# PLL.net
KiCad netlist of a schematic drawn in Altium Designer
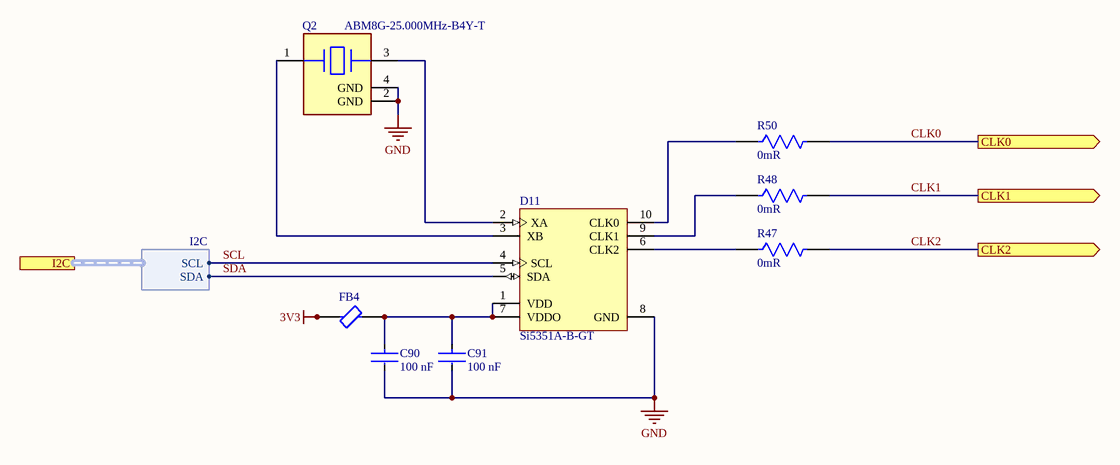
[diagram p0: PLL.SchDoc]

(export (version "E")
  (design (tool "Eeschema 10.0.6"))
  (components
    (comp (ref "C90")
      (value "CC0805KRX7R9BB104")
      (footprint "FP-CC0805-0_85-IPC_A")
      (description "CAP CER 0.1UF 50V X7R 0805")
      (fields (field (name "MANUFACTURER") "Yageo") (field (name "CAPACITANCE") "100 nF"))
      (libsource (lib "SchLib") (part "CMP-2100-03606-3"))
    )
    (comp (ref "C91")
      (value "CC0805KRX7R9BB104")
      (footprint "FP-CC0805-0_85-IPC_A")
      (description "CAP CER 0.1UF 50V X7R 0805")
      (fields (field (name "MANUFACTURER") "Yageo") (field (name "CAPACITANCE") "100 nF"))
      (libsource (lib "SchLib") (part "CMP-2100-03606-3"))
    )
    (comp (ref "D11")
      (value "Si5351A-B-GT")
      (footprint "SLAB-MSOP-10_L")
      (fields
        (field (name "MANUFACTURER") "Silicon Labs")
        (field (name "MANUFACTURER PART NUMBER") "SI5351A-B-GT")
      )
      (libsource (lib "SchLib") (part "CMP-0510-00012-1"))
    )
    (comp (ref "FB4")
      (value "BLM21AG601SN1J")
      (footprint "FP-BLM21-0_2-t0_85-e0_5-IPC_A")
      (description "Chip Ferrite Bead, 0805, 600Ω @ 100MHz, 0.2Ω, 25%, 700mA")
      (fields (field (name "MANUFACTURER") "Murata"))
      (libsource (lib "SchLib") (part "CMP-0686-00643-3"))
    )
    (comp (ref "Q2")
      (value "ABM8G-25.000MHz-B4Y-T")
      (footprint "FP-ABM8G-MFG")
      (description "CRYSTAL 25.0000MHZ 10PF SMD")
      (fields
        (field (name "MANUFACTURER") "Abracon")
        (field (name "MANUFACTURER PART NUMBER") "ABM8G-25.000MHZ-B4Y-T")
      )
      (libsource (lib "SchLib") (part "CMP-27762-000021-1"))
    )
    (comp (ref "R47")
      (value "CR0805-J/-000ELF")
      (footprint "FP-CR0805-IPC_A")
      (description "Thick Film Chip Resistors 0805 0Ω 0.125W 5%")
      (fields (field (name "RESISTANCE") "0mR") (field (name "MANUFACTURER") "Bourns"))
      (libsource (lib "SchLib") (part "CMP-07231-004348-1"))
    )
    (comp (ref "R48")
      (value "CR0805-J/-000ELF")
      (footprint "FP-CR0805-IPC_A")
      (description "Thick Film Chip Resistors 0805 0Ω 0.125W 5%")
      (fields (field (name "RESISTANCE") "0mR") (field (name "MANUFACTURER") "Bourns"))
      (libsource (lib "SchLib") (part "CMP-07231-004348-1"))
    )
    (comp (ref "R50")
      (value "CR0805-J/-000ELF")
      (footprint "FP-CR0805-IPC_A")
      (description "Thick Film Chip Resistors 0805 0Ω 0.125W 5%")
      (fields (field (name "RESISTANCE") "0mR") (field (name "MANUFACTURER") "Bourns"))
      (libsource (lib "SchLib") (part "CMP-07231-004348-1"))
    )
  )
  (nets
    (net (code "2") (name "/CLK0") (class "Default")
      (node (ref "R50") (pin "2") (pinfunction "2_2") (pintype "passive"))
    )
    (net (code "3") (name "/CLK1") (class "Default")
      (node (ref "R48") (pin "2") (pinfunction "2_2") (pintype "passive"))
    )
    (net (code "4") (name "/CLK2") (class "Default")
      (node (ref "R47") (pin "2") (pinfunction "2_2") (pintype "passive"))
    )
    (net (code "5") (name "/SCL") (class "Default")
      (node (ref "D11") (pin "4") (pinfunction "SCL_4") (pintype "input"))
    )
    (net (code "6") (name "/SDA") (class "Default")
      (node (ref "D11") (pin "5") (pinfunction "SDA_5") (pintype "bidirectional"))
    )
    (net (code "8") (name "3V3") (class "Default")
      (node (ref "FB4") (pin "1") (pinfunction "1_1") (pintype "passive"))
    )
    (net (code "9") (name "GND") (class "Default")
      (node (ref "C90") (pin "2") (pinfunction "2_2") (pintype "passive"))
      (node (ref "C91") (pin "2") (pinfunction "2_2") (pintype "passive"))
      (node (ref "D11") (pin "8") (pinfunction "GND_8") (pintype "power_in"))
      (node (ref "Q2") (pin "2") (pinfunction "GND_2") (pintype "power_in"))
      (node (ref "Q2") (pin "4") (pinfunction "GND_4") (pintype "power_in"))
    )
    (net (code "10") (name "Net-(D11-CLK0)") (class "Default")
      (node (ref "D11") (pin "10") (pinfunction "CLK0_10") (pintype "tri_state"))
      (node (ref "R50") (pin "1") (pinfunction "1_1") (pintype "passive"))
    )
    (net (code "11") (name "Net-(D11-CLK1)") (class "Default")
      (node (ref "D11") (pin "9") (pinfunction "CLK1_9") (pintype "tri_state"))
      (node (ref "R48") (pin "1") (pinfunction "1_1") (pintype "passive"))
    )
    (net (code "12") (name "Net-(D11-CLK2)") (class "Default")
      (node (ref "D11") (pin "6") (pinfunction "CLK2_6") (pintype "tri_state"))
      (node (ref "R47") (pin "1") (pinfunction "1_1") (pintype "passive"))
    )
    (net (code "13") (name "Net-(D11-VDD)") (class "Default")
      (node (ref "C90") (pin "1") (pinfunction "1_1") (pintype "passive"))
      (node (ref "C91") (pin "1") (pinfunction "1_1") (pintype "passive"))
      (node (ref "D11") (pin "1") (pinfunction "VDD_1") (pintype "power_in"))
      (node (ref "D11") (pin "7") (pinfunction "VDDO_7") (pintype "power_in"))
      (node (ref "FB4") (pin "2") (pinfunction "2_2") (pintype "passive"))
    )
    (net (code "14") (name "Net-(D11-XA)") (class "Default")
      (node (ref "D11") (pin "2") (pinfunction "XA_2") (pintype "input"))
      (node (ref "Q2") (pin "3") (pinfunction "3_3") (pintype "passive"))
    )
    (net (code "15") (name "Net-(D11-XB)") (class "Default")
      (node (ref "D11") (pin "3") (pinfunction "XB_3") (pintype "passive"))
      (node (ref "Q2") (pin "1") (pinfunction "1_1") (pintype "passive"))
    )
  )
)
